# piggy.net
KiCad netlist of a schematic drawn in EAGLE
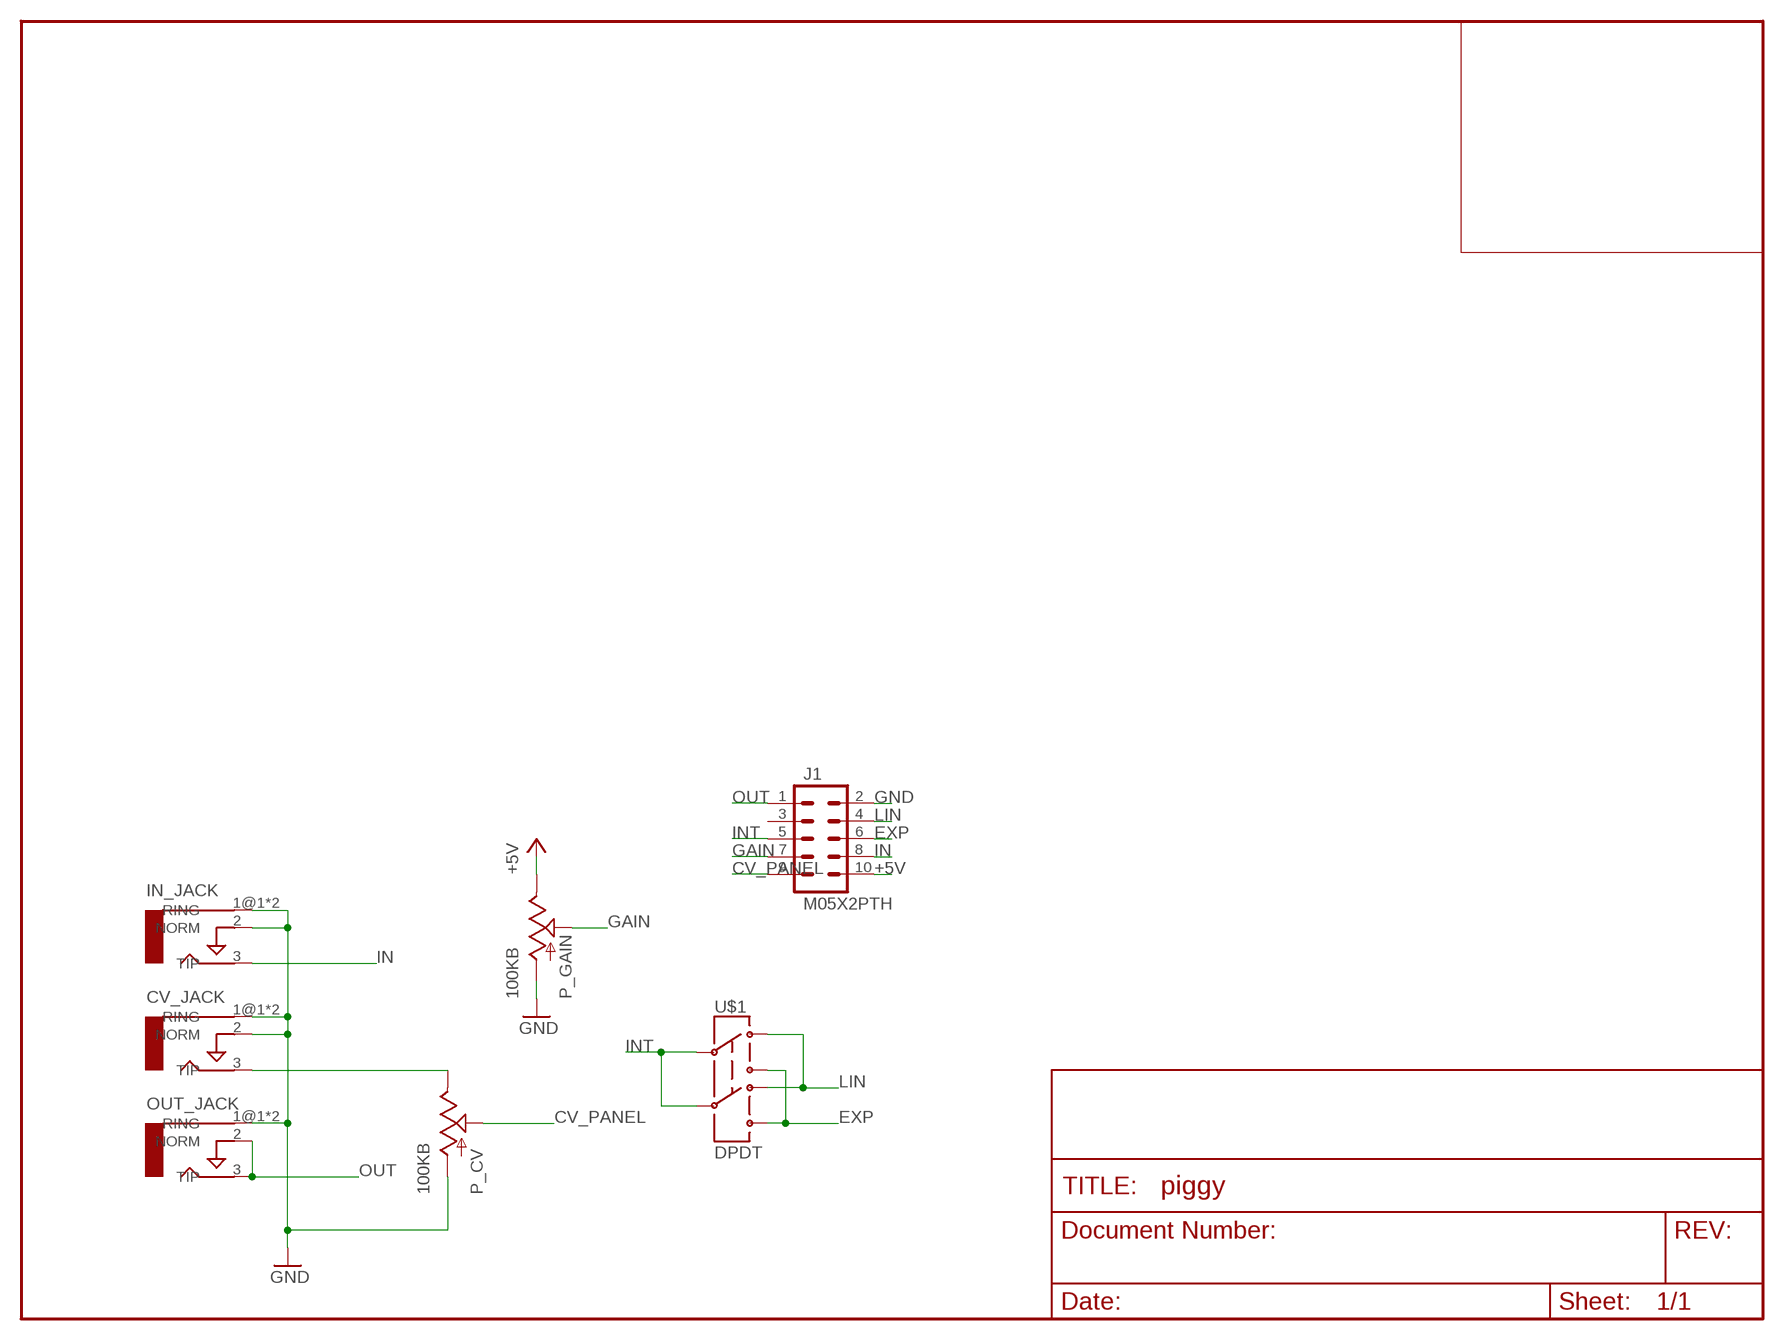
[diagram p0: schematic, sheet 1]

(export (version "E")
  (design (tool "Eeschema 10.0.6"))
  (components
    (comp (ref "CV_JACK")
      (value "AUDIO-JACKERTHENVAR")
      (footprint "eagle-import:ERTHENVAR-JACK")
      (libsource (lib "eagle-import") (part "AUDIO-JACKERTHENVAR"))
    )
    (comp (ref "IN_JACK")
      (value "AUDIO-JACKERTHENVAR")
      (footprint "eagle-import:ERTHENVAR-JACK")
      (libsource (lib "eagle-import") (part "AUDIO-JACKERTHENVAR"))
    )
    (comp (ref "J1")
      (value "M05X2PTH")
      (footprint "eagle-import:AVR_ICSP")
      (libsource (lib "eagle-import") (part "M05X2PTH"))
    )
    (comp (ref "OUT_JACK")
      (value "AUDIO-JACKERTHENVAR")
      (footprint "eagle-import:ERTHENVAR-JACK")
      (libsource (lib "eagle-import") (part "AUDIO-JACKERTHENVAR"))
    )
    (comp (ref "P_CV")
      (value "100KB")
      (footprint "eagle-import:PDB12")
      (libsource (lib "eagle-import") (part "POTPDB12"))
    )
    (comp (ref "P_GAIN")
      (value "100KB")
      (footprint "eagle-import:PDB12")
      (libsource (lib "eagle-import") (part "POTPDB12"))
    )
    (comp (ref "U$1")
      (value "DPDT")
      (footprint "eagle-import:MOUNTAIN_10SL005")
      (libsource (lib "eagle-import") (part "DPDT"))
    )
  )
  (nets
    (net (code "1") (name "+5V") (class "Default")
      (node (ref "J1") (pin "10") (pinfunction "10_10") (pintype "passive"))
      (node (ref "P_GAIN") (pin "3") (pinfunction "E_3") (pintype "passive"))
    )
    (net (code "2") (name "/CV_PANEL") (class "Default")
      (node (ref "J1") (pin "9") (pinfunction "9_9") (pintype "passive"))
      (node (ref "P_CV") (pin "2") (pinfunction "S_2") (pintype "passive"))
    )
    (net (code "3") (name "/EXP") (class "Default")
      (node (ref "J1") (pin "6") (pinfunction "6_6") (pintype "passive"))
      (node (ref "U$1") (pin "Y1") (pinfunction "Y1_Y1") (pintype "bidirectional"))
      (node (ref "U$1") (pin "Y2") (pinfunction "Y2_Y2") (pintype "bidirectional"))
    )
    (net (code "4") (name "/GAIN") (class "Default")
      (node (ref "J1") (pin "7") (pinfunction "7_7") (pintype "passive"))
      (node (ref "P_GAIN") (pin "2") (pinfunction "S_2") (pintype "passive"))
    )
    (net (code "5") (name "/IN") (class "Default")
      (node (ref "IN_JACK") (pin "3") (pinfunction "TIP_3") (pintype "bidirectional"))
      (node (ref "J1") (pin "8") (pinfunction "8_8") (pintype "passive"))
    )
    (net (code "6") (name "/INT") (class "Default")
      (node (ref "J1") (pin "5") (pinfunction "5_5") (pintype "passive"))
      (node (ref "U$1") (pin "C1") (pinfunction "C1_C1") (pintype "bidirectional"))
      (node (ref "U$1") (pin "C2") (pinfunction "C2_C2") (pintype "bidirectional"))
    )
    (net (code "7") (name "/LIN") (class "Default")
      (node (ref "J1") (pin "4") (pinfunction "4_4") (pintype "passive"))
      (node (ref "U$1") (pin "X1") (pinfunction "X1_X1") (pintype "bidirectional"))
      (node (ref "U$1") (pin "X2") (pinfunction "X2_X2") (pintype "bidirectional"))
    )
    (net (code "8") (name "/OUT") (class "Default")
      (node (ref "J1") (pin "1") (pinfunction "1_1") (pintype "passive"))
      (node (ref "OUT_JACK") (pin "2") (pinfunction "NORM_2") (pintype "bidirectional"))
      (node (ref "OUT_JACK") (pin "3") (pinfunction "TIP_3") (pintype "bidirectional"))
    )
    (net (code "9") (name "GND") (class "Default")
      (node (ref "CV_JACK") (pin "1@1") (pinfunction "RING_1@1") (pintype "bidirectional"))
      (node (ref "CV_JACK") (pin "1@2") (pinfunction "RING_1@2") (pintype "bidirectional"))
      (node (ref "CV_JACK") (pin "2") (pinfunction "NORM_2") (pintype "bidirectional"))
      (node (ref "IN_JACK") (pin "1@1") (pinfunction "RING_1@1") (pintype "bidirectional"))
      (node (ref "IN_JACK") (pin "1@2") (pinfunction "RING_1@2") (pintype "bidirectional"))
      (node (ref "IN_JACK") (pin "2") (pinfunction "NORM_2") (pintype "bidirectional"))
      (node (ref "J1") (pin "2") (pinfunction "2_2") (pintype "passive"))
      (node (ref "OUT_JACK") (pin "1@1") (pinfunction "RING_1@1") (pintype "bidirectional"))
      (node (ref "OUT_JACK") (pin "1@2") (pinfunction "RING_1@2") (pintype "bidirectional"))
      (node (ref "P_CV") (pin "1") (pinfunction "A_1") (pintype "passive"))
      (node (ref "P_GAIN") (pin "1") (pinfunction "A_1") (pintype "passive"))
    )
    (net (code "10") (name "Net-(CV_JACK-TIP)") (class "Default")
      (node (ref "CV_JACK") (pin "3") (pinfunction "TIP_3") (pintype "bidirectional"))
      (node (ref "P_CV") (pin "3") (pinfunction "E_3") (pintype "passive"))
    )
    (net (code "11") (name "unconnected-(J1-Pad3)") (class "Default")
      (node (ref "J1") (pin "3") (pinfunction "3_3") (pintype "passive"))
    )
  )
)
